# McPiFace-Pi-4-Audio-V2_0.net
KiCad netlist of a schematic drawn in EAGLE
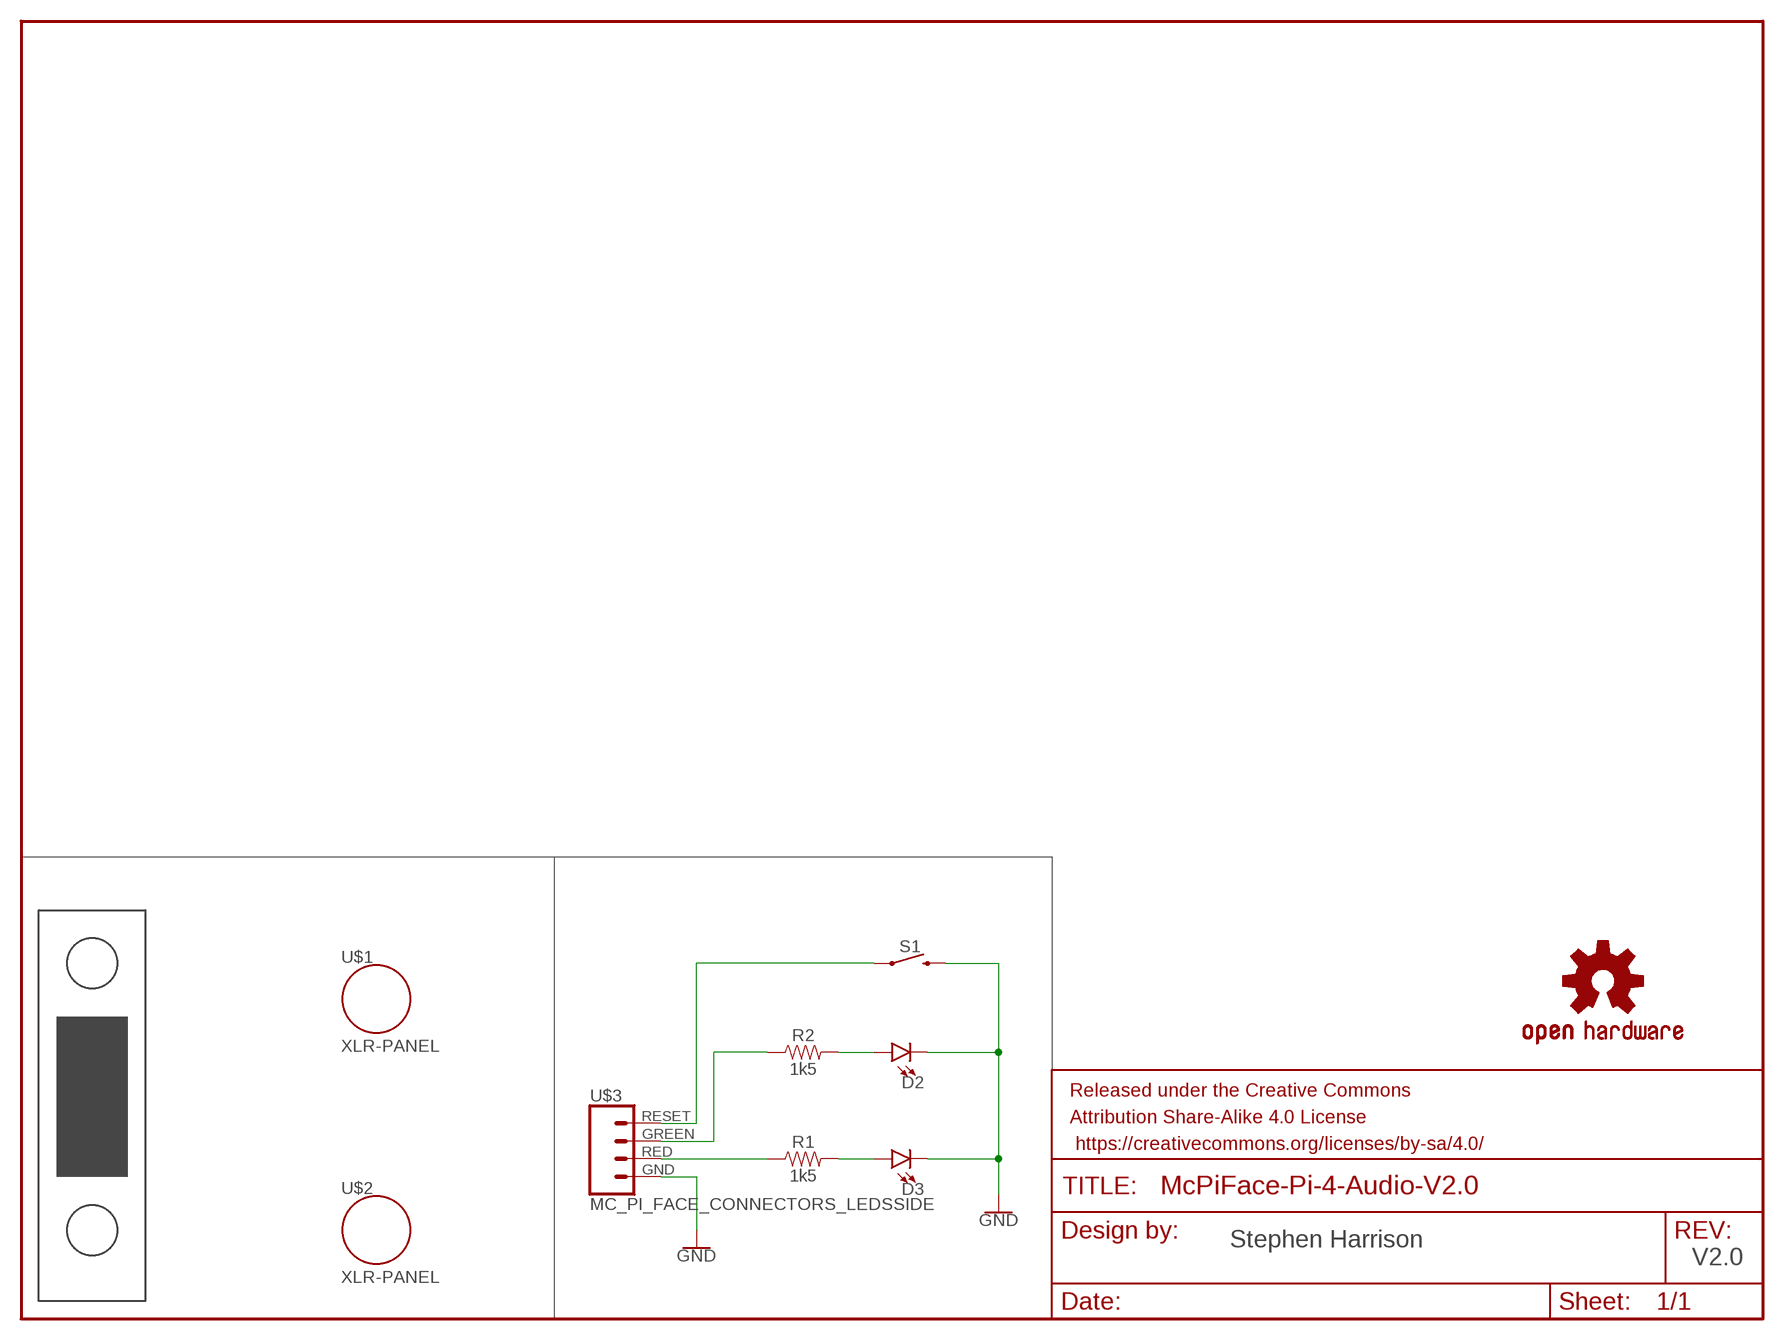
[diagram p0: schematic, sheet 1]

(export (version "E")
  (design (tool "Eeschema 10.0.6"))
  (components
    (comp (ref "D2")
      (value "LEDLED-1206-BOTTOM-2.0MM-GREEN")
      (footprint "eagle-import:LED-1206-BOTTOM-2.0MM")
      (libsource (lib "eagle-import") (part "LEDLED-1206-BOTTOM-2.0MM-GREEN"))
    )
    (comp (ref "D3")
      (value "LEDLED-1206-BOTTOM-2.0MM-RED")
      (footprint "eagle-import:LED-1206-BOTTOM-2.0MM")
      (libsource (lib "eagle-import") (part "LEDLED-1206-BOTTOM-2.0MM-RED"))
    )
    (comp (ref "FRAME1")
      (value "FRAME-LETTER")
      (footprint "eagle-import:CREATIVE_COMMONS")
      (libsource (lib "eagle-import") (part "FRAME-LETTER"))
    )
    (comp (ref "LOGO1")
      (value "OSHW-LOGOL")
      (footprint "eagle-import:OSHW-LOGO-L")
      (libsource (lib "eagle-import") (part "OSHW-LOGOL"))
    )
    (comp (ref "R1")
      (value "1k5")
      (footprint "eagle-import:0805")
      (libsource (lib "eagle-import") (part "RESISTOR0805"))
    )
    (comp (ref "R2")
      (value "1k5")
      (footprint "eagle-import:0805")
      (libsource (lib "eagle-import") (part "RESISTOR0805"))
    )
    (comp (ref "S1")
      (value "MOMENTARY-SWITCH-SPSTTACKTILE_SWITCH_PTH_6.0MM_NO_TOP_RESIST")
      (footprint "eagle-import:TACTILE_SWITCH_PTH_6.0MM_NO_TOP_RESIST")
      (libsource (lib "eagle-import") (part "MOMENTARY-SWITCH-SPSTTACKTILE_SWITCH_PTH_6.0MM_NO_TOP_RESIST"))
    )
    (comp (ref "U$1")
      (value "XLR-PANEL")
      (footprint "eagle-import:NC3FD-V-BAG-PANEL-COUTOUT")
      (libsource (lib "eagle-import") (part "XLR-PANEL"))
    )
    (comp (ref "U$2")
      (value "XLR-PANEL")
      (footprint "eagle-import:NC3FD-V-BAG-PANEL-COUTOUT")
      (libsource (lib "eagle-import") (part "XLR-PANEL"))
    )
    (comp (ref "U$3")
      (value "MC_PI_FACE_CONNECTORS_LEDSSIDE")
      (footprint "eagle-import:JST-4-SH-1.0MM-SIDE")
      (fields (field (name "MFG") "SM04B-SRSS-TB(LF)(SN)"))
      (libsource (lib "eagle-import") (part "MC_PI_FACE_CONNECTORS_LEDSSIDE"))
    )
    (comp (ref "U$4")
      (value "MC_PI_4_FACE_PANELDOUBLE")
      (footprint "eagle-import:MC_PI_4-DOUBLE_FACE")
      (libsource (lib "eagle-import") (part "MC_PI_4_FACE_PANELDOUBLE"))
    )
  )
  (nets
    (net (code "1") (name "GND") (class "Default")
      (node (ref "D2") (pin "C") (pinfunction "C_C") (pintype "passive"))
      (node (ref "D3") (pin "C") (pinfunction "C_C") (pintype "passive"))
      (node (ref "S1") (pin "3") (pinfunction "2_3") (pintype "passive"))
      (node (ref "U$3") (pin "GND") (pinfunction "GND_GND") (pintype "power_in"))
    )
    (net (code "2") (name "Net-(D2-PadA)") (class "Default")
      (node (ref "D2") (pin "A") (pinfunction "A_A") (pintype "passive"))
      (node (ref "R2") (pin "2") (pinfunction "2_2") (pintype "passive"))
    )
    (net (code "3") (name "Net-(D3-PadA)") (class "Default")
      (node (ref "D3") (pin "A") (pinfunction "A_A") (pintype "passive"))
      (node (ref "R1") (pin "2") (pinfunction "2_2") (pintype "passive"))
    )
    (net (code "4") (name "Net-(R1-Pad1)") (class "Default")
      (node (ref "R1") (pin "1") (pinfunction "1_1") (pintype "passive"))
      (node (ref "U$3") (pin "RED") (pinfunction "RED_RED") (pintype "passive"))
    )
    (net (code "5") (name "Net-(R2-Pad1)") (class "Default")
      (node (ref "R2") (pin "1") (pinfunction "1_1") (pintype "passive"))
      (node (ref "U$3") (pin "GREEN") (pinfunction "GREEN_GREEN") (pintype "passive"))
    )
    (net (code "6") (name "Net-(S1-Pad1)") (class "Default")
      (node (ref "S1") (pin "1") (pinfunction "1_1") (pintype "passive"))
      (node (ref "U$3") (pin "RESET") (pinfunction "RESET_RESET") (pintype "passive"))
    )
  )
)
